# Toslink_Transceiver_V3.net
KiCad netlist of a schematic drawn in EAGLE
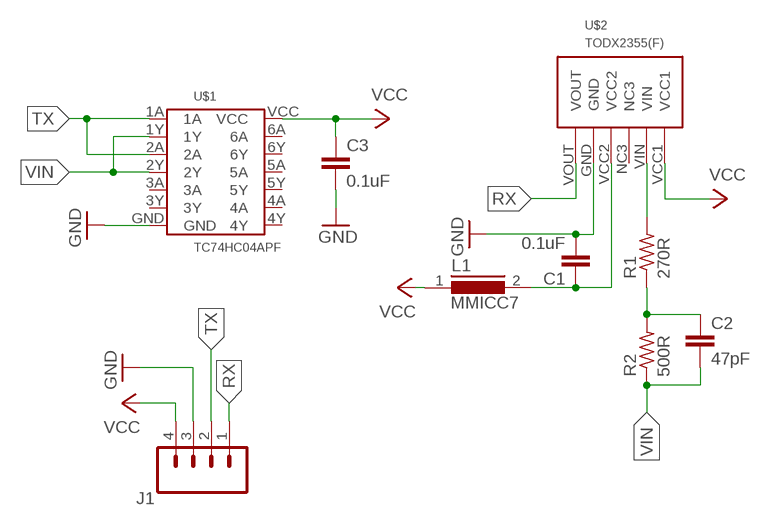
[diagram p0: schematic, sheet 1]

(export (version "E")
  (design (tool "Eeschema 10.0.6"))
  (components
    (comp (ref "C1")
      (value "0.1uF")
      (footprint "eagle-import:C2.5-2")
      (libsource (lib "eagle-import") (part "C2.5/2"))
    )
    (comp (ref "C2")
      (value "47pF")
      (footprint "eagle-import:C2.5-2")
      (libsource (lib "eagle-import") (part "C2.5/2"))
    )
    (comp (ref "C3")
      (value "0.1uF")
      (footprint "eagle-import:C2.5-2")
      (libsource (lib "eagle-import") (part "C2.5/2"))
    )
    (comp (ref "J1")
      (value "CONN_04")
      (footprint "eagle-import:1X04")
      (libsource (lib "eagle-import") (part "CONN_04"))
    )
    (comp (ref "L1")
      (value "MMICC7")
      (footprint "eagle-import:MMICC7")
      (libsource (lib "eagle-import") (part "MMICC7"))
    )
    (comp (ref "R1")
      (value "270R")
      (footprint "eagle-import:0204_5")
      (libsource (lib "eagle-import") (part "R-US_0204/5"))
    )
    (comp (ref "R2")
      (value "500R")
      (footprint "eagle-import:0204_5")
      (libsource (lib "eagle-import") (part "R-US_0204/5"))
    )
    (comp (ref "U$1")
      (value "TC74HC04APF")
      (footprint "eagle-import:DIP14-P-300-2.54")
      (libsource (lib "eagle-import") (part "TC74HC04APF"))
    )
    (comp (ref "U$2")
      (value "TODX2355(F)")
      (footprint "eagle-import:TODX2355(F)")
      (libsource (lib "eagle-import") (part "TODX2355(F)"))
    )
  )
  (nets
    (net (code "1") (name "GND") (class "Default")
      (node (ref "C1") (pin "2") (pinfunction "2_2") (pintype "passive"))
      (node (ref "C3") (pin "2") (pinfunction "2_2") (pintype "passive"))
      (node (ref "J1") (pin "3") (pinfunction "3_3") (pintype "passive"))
      (node (ref "U$1") (pin "GND") (pinfunction "GND_GND") (pintype "bidirectional"))
      (node (ref "U$2") (pin "GND") (pinfunction "GND_GND") (pintype "bidirectional"))
    )
    (net (code "2") (name "Net-(C1-Pad1)") (class "Default")
      (node (ref "C1") (pin "1") (pinfunction "1_1") (pintype "passive"))
      (node (ref "L1") (pin "2") (pinfunction "2_2") (pintype "passive"))
      (node (ref "U$2") (pin "VCC2") (pinfunction "VCC2_VCC2") (pintype "bidirectional"))
    )
    (net (code "3") (name "Net-(C2-Pad1)") (class "Default")
      (node (ref "C2") (pin "1") (pinfunction "1_1") (pintype "passive"))
      (node (ref "R1") (pin "1") (pinfunction "1_1") (pintype "passive"))
      (node (ref "R2") (pin "2") (pinfunction "2_2") (pintype "passive"))
    )
    (net (code "4") (name "Net-(R1-Pad2)") (class "Default")
      (node (ref "R1") (pin "2") (pinfunction "2_2") (pintype "passive"))
      (node (ref "U$2") (pin "VIN") (pinfunction "VIN_VIN") (pintype "bidirectional"))
    )
    (net (code "5") (name "RX") (class "Default")
      (node (ref "J1") (pin "1") (pinfunction "1_1") (pintype "passive"))
      (node (ref "U$2") (pin "VOUT") (pinfunction "VOUT_VOUT") (pintype "bidirectional"))
    )
    (net (code "6") (name "TX") (class "Default")
      (node (ref "J1") (pin "2") (pinfunction "2_2") (pintype "passive"))
      (node (ref "U$1") (pin "1A") (pinfunction "1A_1A") (pintype "bidirectional"))
      (node (ref "U$1") (pin "2A") (pinfunction "2A_2A") (pintype "bidirectional"))
    )
    (net (code "7") (name "VCC") (class "Default")
      (node (ref "C3") (pin "1") (pinfunction "1_1") (pintype "passive"))
      (node (ref "J1") (pin "4") (pinfunction "4_4") (pintype "passive"))
      (node (ref "L1") (pin "1") (pinfunction "1_1") (pintype "passive"))
      (node (ref "U$1") (pin "VCC") (pinfunction "VCC_VCC") (pintype "bidirectional"))
      (node (ref "U$2") (pin "VCC1") (pinfunction "VCC1_VCC1") (pintype "bidirectional"))
    )
    (net (code "8") (name "VIN") (class "Default")
      (node (ref "C2") (pin "2") (pinfunction "2_2") (pintype "passive"))
      (node (ref "R2") (pin "1") (pinfunction "1_1") (pintype "passive"))
      (node (ref "U$1") (pin "1Y") (pinfunction "1Y_1Y") (pintype "bidirectional"))
      (node (ref "U$1") (pin "2Y") (pinfunction "2Y_2Y") (pintype "bidirectional"))
    )
    (net (code "9") (name "unconnected-(U$1-Pad3A)") (class "Default")
      (node (ref "U$1") (pin "3A") (pinfunction "3A_3A") (pintype "bidirectional"))
    )
    (net (code "10") (name "unconnected-(U$1-Pad3Y)") (class "Default")
      (node (ref "U$1") (pin "3Y") (pinfunction "3Y_3Y") (pintype "bidirectional"))
    )
    (net (code "11") (name "unconnected-(U$1-Pad4A)") (class "Default")
      (node (ref "U$1") (pin "4A") (pinfunction "4A_4A") (pintype "bidirectional"))
    )
    (net (code "12") (name "unconnected-(U$1-Pad4Y)") (class "Default")
      (node (ref "U$1") (pin "4Y") (pinfunction "4Y_4Y") (pintype "bidirectional"))
    )
    (net (code "13") (name "unconnected-(U$1-Pad5A)") (class "Default")
      (node (ref "U$1") (pin "5A") (pinfunction "5A_5A") (pintype "bidirectional"))
    )
    (net (code "14") (name "unconnected-(U$1-Pad5Y)") (class "Default")
      (node (ref "U$1") (pin "5Y") (pinfunction "5Y_5Y") (pintype "bidirectional"))
    )
    (net (code "15") (name "unconnected-(U$1-Pad6A)") (class "Default")
      (node (ref "U$1") (pin "6A") (pinfunction "6A_6A") (pintype "bidirectional"))
    )
    (net (code "16") (name "unconnected-(U$1-Pad6Y)") (class "Default")
      (node (ref "U$1") (pin "6Y") (pinfunction "6Y_6Y") (pintype "bidirectional"))
    )
    (net (code "17") (name "unconnected-(U$2-PadNC3)") (class "Default")
      (node (ref "U$2") (pin "NC3") (pinfunction "NC3_NC3") (pintype "bidirectional"))
    )
  )
)
